# ft311d.net
KiCad netlist of a schematic drawn in Altium Designer
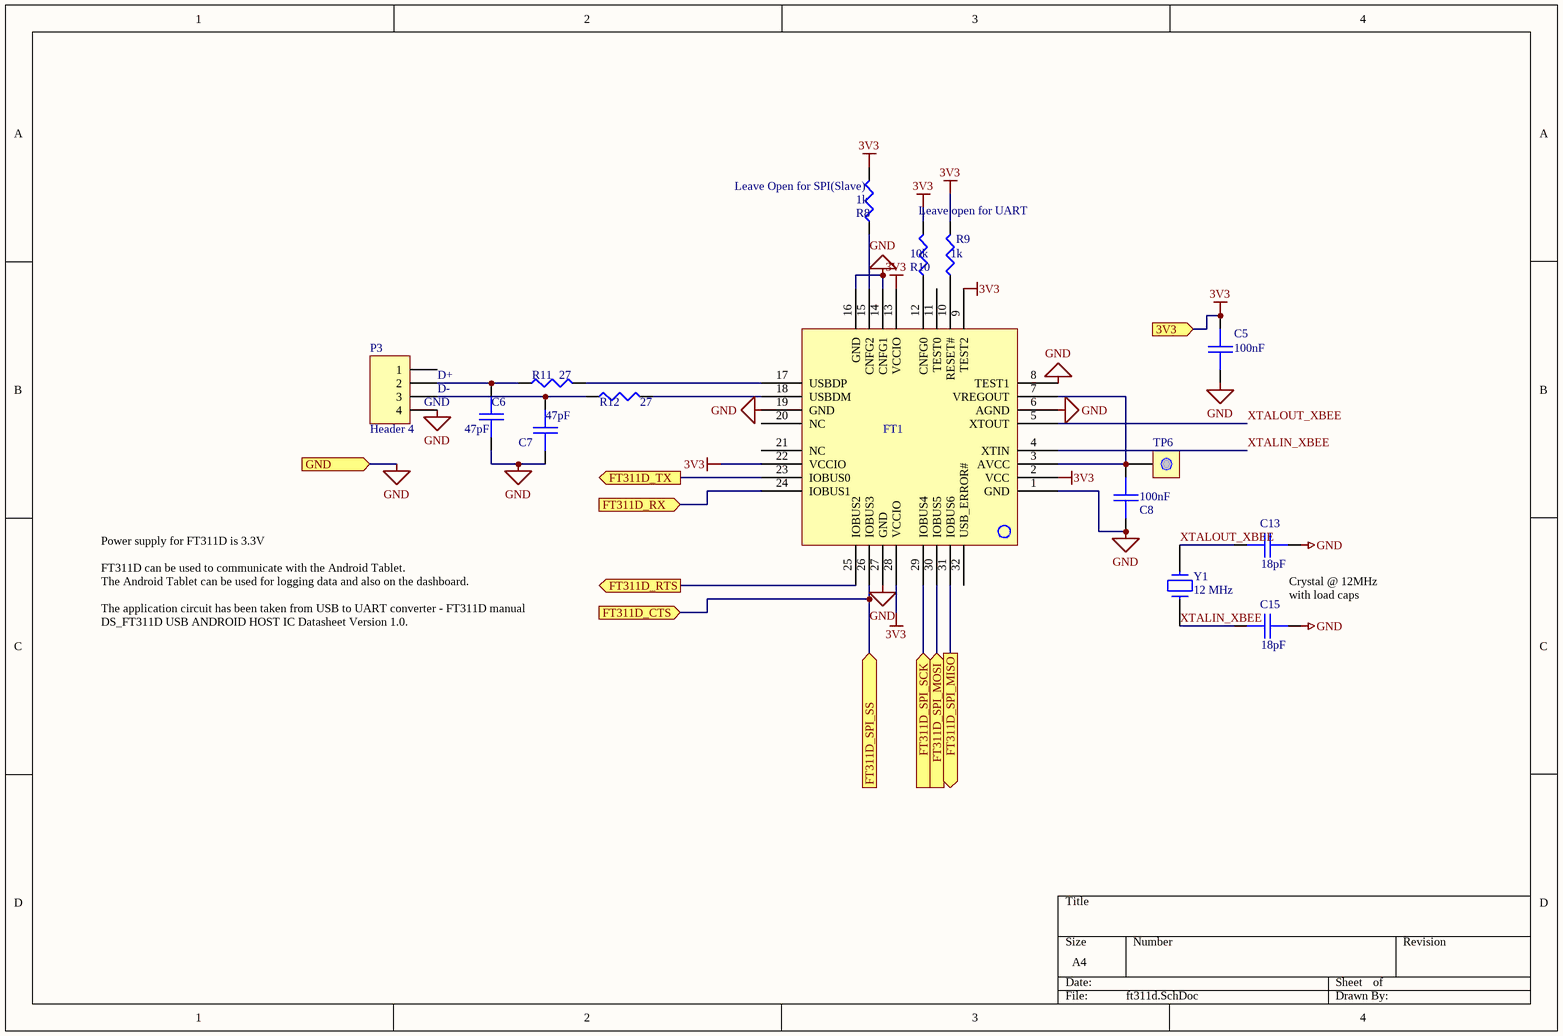
[diagram p0: ft311d.SchDoc]

(export (version "E")
  (design (tool "Eeschema 10.0.6"))
  (components
    (comp (ref "C5")
      (value "100nF")
      (footprint "0603")
      (description "Capacitor")
      (fields (field (name "Comment") "CAP"))
      (libsource (lib "RCLDQ") (part "CAP"))
    )
    (comp (ref "C6")
      (value "47pF")
      (footprint "0603")
      (description "Capacitor")
      (fields (field (name "Comment") "CAP"))
      (libsource (lib "RCLDQ") (part "CAP"))
    )
    (comp (ref "C7")
      (value "47pF")
      (footprint "0603")
      (description "Capacitor")
      (fields (field (name "Comment") "CAP"))
      (libsource (lib "RCLDQ") (part "CAP"))
    )
    (comp (ref "C8")
      (value "100nF")
      (footprint "0603")
      (description "Capacitor")
      (fields (field (name "Comment") "CAP"))
      (libsource (lib "RCLDQ") (part "CAP"))
    )
    (comp (ref "C13")
      (value "18pF")
      (footprint "0603")
      (description "Capacitor")
      (fields (field (name "Comment") "CAP"))
      (libsource (lib "RCLDQ") (part "CAP"))
    )
    (comp (ref "C15")
      (value "18pF")
      (footprint "0603")
      (description "Capacitor")
      (fields (field (name "Comment") "CAP"))
      (libsource (lib "RCLDQ") (part "CAP"))
    )
    (comp (ref "FT1")
      (value "FT311D")
      (footprint "QFP32")
      (description "USB ANDROID Host IC")
      (fields (field (name "MANUFACTURER PART NO") "FT311D-32L1C-R-IC"))
      (libsource (lib "add-schematic-library") (part "FT311D"))
    )
    (comp (ref "P3")
      (value "Header 4")
      (footprint "HDR1X4")
      (description "Header, 4-Pin")
      (fields (field (name "PUBLISHER") "Altium Limited"))
      (libsource (lib "Miscellaneous Connectors") (part "Header 4"))
    )
    (comp (ref "R8")
      (value "Leave Open for SPI(Slave)")
      (footprint "0603")
      (description "Resistor")
      (fields (field (name "ALTIUM_VALUE") "1k"))
      (libsource (lib "RCLDQ") (part "RES1"))
    )
    (comp (ref "R9")
      (value "1k")
      (footprint "0603")
      (description "Resistor")
      (fields (field (name "Comment") "RES1"))
      (libsource (lib "RCLDQ") (part "RES1"))
    )
    (comp (ref "R10")
      (value "Leave open for UART")
      (footprint "0603")
      (description "Resistor")
      (fields (field (name "ALTIUM_VALUE") "10k"))
      (libsource (lib "RCLDQ") (part "RES1"))
    )
    (comp (ref "R11")
      (value "27")
      (footprint "0603")
      (description "Resistor")
      (libsource (lib "RCLDQ") (part "RES1"))
    )
    (comp (ref "R12")
      (value "27")
      (footprint "0603")
      (description "Resistor")
      (fields (field (name "Comment") "RES1"))
      (libsource (lib "RCLDQ") (part "RES1"))
    )
    (comp (ref "TP6")
      (value "TP_AVCC")
      (footprint "TESTPOINT")
      (description "TEST POINT")
      (libsource (lib "Miscellaneous") (part "TEST"))
    )
    (comp (ref "Y1")
      (value "12 MHz")
      (footprint "HC49/4H")
      (description "Crystal")
      (libsource (lib "*") (part "CRYSTAL"))
    )
  )
  (nets
    (net (code "1") (name "/FT311D_CTS") (class "Default")
      (node (ref "FT1") (pin "26") (pinfunction "IOBUS3_26") (pintype "passive"))
    )
    (net (code "2") (name "/FT311D_RTS") (class "Default")
      (node (ref "FT1") (pin "25") (pinfunction "IOBUS2_25") (pintype "passive"))
    )
    (net (code "3") (name "/FT311D_RX") (class "Default")
      (node (ref "FT1") (pin "24") (pinfunction "IOBUS1_24") (pintype "passive"))
    )
    (net (code "4") (name "/FT311D_SPI_MISO") (class "Default")
      (node (ref "FT1") (pin "31") (pinfunction "IOBUS6_31") (pintype "passive"))
    )
    (net (code "5") (name "/FT311D_SPI_MOSI") (class "Default")
      (node (ref "FT1") (pin "30") (pinfunction "IOBUS5_30") (pintype "passive"))
    )
    (net (code "6") (name "/FT311D_SPI_SCK") (class "Default")
      (node (ref "FT1") (pin "29") (pinfunction "IOBUS4_29") (pintype "passive"))
    )
    (net (code "7") (name "/FT311D_TX") (class "Default")
      (node (ref "FT1") (pin "23") (pinfunction "IOBUS0_23") (pintype "passive"))
    )
    (net (code "8") (name "/XTALIN_XBEE") (class "Default")
      (node (ref "C15") (pin "1") (pinfunction "1_1") (pintype "passive"))
      (node (ref "FT1") (pin "4") (pinfunction "XTIN_4") (pintype "passive"))
      (node (ref "Y1") (pin "1") (pinfunction "1_1") (pintype "passive"))
    )
    (net (code "9") (name "/XTALOUT_XBEE") (class "Default")
      (node (ref "C13") (pin "1") (pinfunction "1_1") (pintype "passive"))
      (node (ref "FT1") (pin "5") (pinfunction "XTOUT_5") (pintype "passive"))
      (node (ref "Y1") (pin "2") (pinfunction "2_2") (pintype "passive"))
    )
    (net (code "10") (name "3V3") (class "Default")
      (node (ref "C5") (pin "1") (pinfunction "1_1") (pintype "passive"))
      (node (ref "FT1") (pin "13") (pinfunction "VCCIO_13") (pintype "passive"))
      (node (ref "FT1") (pin "2") (pinfunction "VCC_2") (pintype "passive"))
      (node (ref "FT1") (pin "22") (pinfunction "VCCIO_22") (pintype "passive"))
      (node (ref "FT1") (pin "28") (pinfunction "VCCIO_28") (pintype "passive"))
      (node (ref "FT1") (pin "9") (pinfunction "TEST2_9") (pintype "passive"))
      (node (ref "R10") (pin "2") (pinfunction "2_2") (pintype "passive"))
      (node (ref "R8") (pin "2") (pinfunction "2_2") (pintype "passive"))
      (node (ref "R9") (pin "2") (pinfunction "2_2") (pintype "passive"))
    )
    (net (code "11") (name "GND") (class "Default")
      (node (ref "C13") (pin "2") (pinfunction "2_2") (pintype "passive"))
      (node (ref "C15") (pin "2") (pinfunction "2_2") (pintype "passive"))
      (node (ref "C5") (pin "2") (pinfunction "2_2") (pintype "passive"))
      (node (ref "C6") (pin "2") (pinfunction "2_2") (pintype "passive"))
      (node (ref "C7") (pin "2") (pinfunction "2_2") (pintype "passive"))
      (node (ref "C8") (pin "2") (pinfunction "2_2") (pintype "passive"))
      (node (ref "FT1") (pin "1") (pinfunction "GND_1") (pintype "passive"))
      (node (ref "FT1") (pin "14") (pinfunction "CNFG1_14") (pintype "passive"))
      (node (ref "FT1") (pin "16") (pinfunction "GND_16") (pintype "passive"))
      (node (ref "FT1") (pin "19") (pinfunction "GND_19") (pintype "passive"))
      (node (ref "FT1") (pin "27") (pinfunction "GND_27") (pintype "passive"))
      (node (ref "FT1") (pin "6") (pinfunction "AGND_6") (pintype "passive"))
      (node (ref "FT1") (pin "8") (pinfunction "TEST1_8") (pintype "passive"))
      (node (ref "P3") (pin "4") (pinfunction "4_4") (pintype "passive"))
    )
    (net (code "12") (name "Net-(C6-Pad1)") (class "Default")
      (node (ref "C6") (pin "1") (pinfunction "1_1") (pintype "passive"))
      (node (ref "P3") (pin "2") (pinfunction "2_2") (pintype "passive"))
      (node (ref "R11") (pin "1") (pinfunction "1_1") (pintype "passive"))
    )
    (net (code "13") (name "Net-(C7-Pad1)") (class "Default")
      (node (ref "C7") (pin "1") (pinfunction "1_1") (pintype "passive"))
      (node (ref "P3") (pin "3") (pinfunction "3_3") (pintype "passive"))
      (node (ref "R12") (pin "1") (pinfunction "1_1") (pintype "passive"))
    )
    (net (code "14") (name "Net-(FT1-AVCC)") (class "Default")
      (node (ref "C8") (pin "1") (pinfunction "1_1") (pintype "passive"))
      (node (ref "FT1") (pin "3") (pinfunction "AVCC_3") (pintype "passive"))
      (node (ref "FT1") (pin "7") (pinfunction "VREGOUT_7") (pintype "passive"))
      (node (ref "TP6") (pin "0") (pinfunction "TP_0") (pintype "passive"))
    )
    (net (code "15") (name "Net-(FT1-CNFG0)") (class "Default")
      (node (ref "FT1") (pin "12") (pinfunction "CNFG0_12") (pintype "passive"))
      (node (ref "R10") (pin "1") (pinfunction "1_1") (pintype "passive"))
    )
    (net (code "16") (name "Net-(FT1-CNFG2)") (class "Default")
      (node (ref "FT1") (pin "15") (pinfunction "CNFG2_15") (pintype "passive"))
      (node (ref "R8") (pin "1") (pinfunction "1_1") (pintype "passive"))
    )
    (net (code "17") (name "Net-(FT1-RESET#)") (class "Default")
      (node (ref "FT1") (pin "10") (pinfunction "RESET#_10") (pintype "passive"))
      (node (ref "R9") (pin "1") (pinfunction "1_1") (pintype "passive"))
    )
    (net (code "18") (name "Net-(FT1-USBDM)") (class "Default")
      (node (ref "FT1") (pin "18") (pinfunction "USBDM_18") (pintype "passive"))
      (node (ref "R12") (pin "2") (pinfunction "2_2") (pintype "passive"))
    )
    (net (code "19") (name "Net-(FT1-USBDP)") (class "Default")
      (node (ref "FT1") (pin "17") (pinfunction "USBDP_17") (pintype "passive"))
      (node (ref "R11") (pin "2") (pinfunction "2_2") (pintype "passive"))
    )
    (net (code "20") (name "unconnected-(FT1-NC-Pad20)") (class "Default")
      (node (ref "FT1") (pin "20") (pinfunction "NC_20") (pintype "passive"))
    )
    (net (code "21") (name "unconnected-(FT1-NC-Pad21)") (class "Default")
      (node (ref "FT1") (pin "21") (pinfunction "NC_21") (pintype "passive"))
    )
    (net (code "22") (name "unconnected-(FT1-TEST0-Pad11)") (class "Default")
      (node (ref "FT1") (pin "11") (pinfunction "TEST0_11") (pintype "passive"))
    )
    (net (code "23") (name "unconnected-(FT1-USB_ERROR#-Pad32)") (class "Default")
      (node (ref "FT1") (pin "32") (pinfunction "USB_ERROR#_32") (pintype "passive"))
    )
    (net (code "24") (name "unconnected-(P3-Pad1)") (class "Default")
      (node (ref "P3") (pin "1") (pinfunction "1_1") (pintype "passive"))
    )
  )
)
